# Line_detector_sensor.net
KiCad netlist of a schematic drawn in Altium Designer
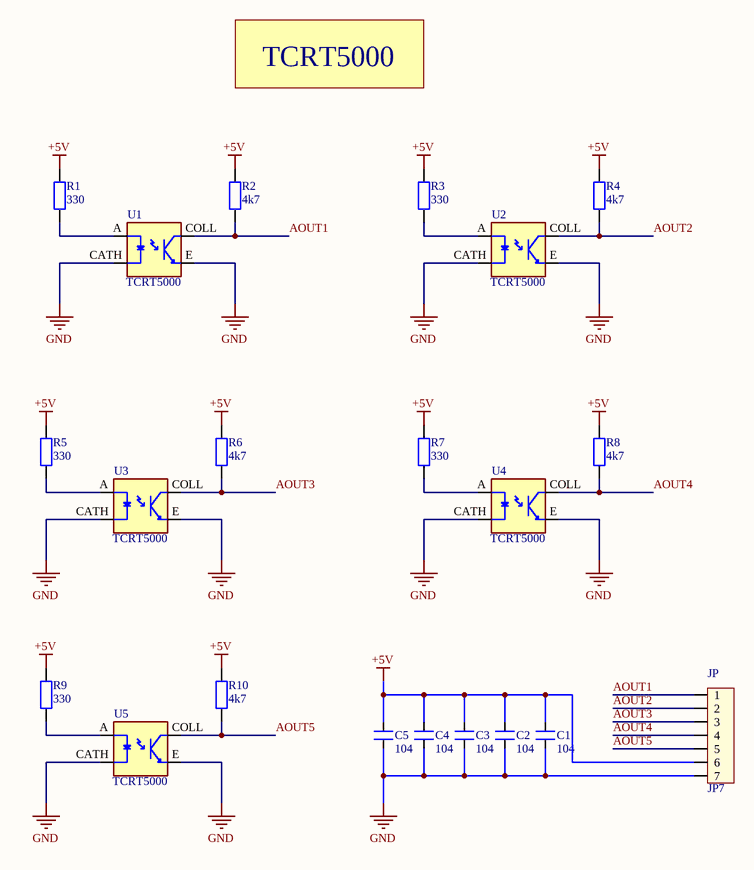
[diagram p0: Line_detector_sensor.SchDoc]

(export (version "E")
  (design (tool "Eeschema 10.0.6"))
  (components
    (comp (ref "C1")
      (value "104")
      (footprint "CN2")
      (description "Cap np 104 => 105pF")
      (libsource (lib "syhaunguyen") (part "CN2"))
    )
    (comp (ref "C2")
      (value "104")
      (footprint "CN2")
      (description "Cap np 104 => 105pF")
      (libsource (lib "syhaunguyen") (part "CN2"))
    )
    (comp (ref "C3")
      (value "104")
      (footprint "CN2")
      (description "Cap np 104 => 105pF")
      (libsource (lib "syhaunguyen") (part "CN2"))
    )
    (comp (ref "C4")
      (value "104")
      (footprint "CN2")
      (description "Cap np 104 => 105pF")
      (libsource (lib "syhaunguyen") (part "CN2"))
    )
    (comp (ref "C5")
      (value "104")
      (footprint "CN2")
      (description "Cap np 104 => 105pF")
      (libsource (lib "syhaunguyen") (part "CN2"))
    )
    (comp (ref "JP")
      (value "JP7")
      (footprint "CON7")
      (description "Connector 7")
      (libsource (lib "syhaunguyen") (part "Con7"))
    )
    (comp (ref "R1")
      (value "330")
      (footprint "R1/4W")
      (description "Resistor 1/4W")
      (libsource (lib "syhaunguyen") (part "R1/4W"))
    )
    (comp (ref "R2")
      (value "4k7")
      (footprint "R1/4W")
      (description "Resistor 1/4W")
      (libsource (lib "syhaunguyen") (part "R1/4W"))
    )
    (comp (ref "R3")
      (value "330")
      (footprint "R1/4W")
      (description "Resistor 1/4W")
      (libsource (lib "syhaunguyen") (part "R1/4W"))
    )
    (comp (ref "R4")
      (value "4k7")
      (footprint "R1/4W")
      (description "Resistor 1/4W")
      (libsource (lib "syhaunguyen") (part "R1/4W"))
    )
    (comp (ref "R5")
      (value "330")
      (footprint "R1/4W")
      (description "Resistor 1/4W")
      (libsource (lib "syhaunguyen") (part "R1/4W"))
    )
    (comp (ref "R6")
      (value "4k7")
      (footprint "R1/4W")
      (description "Resistor 1/4W")
      (libsource (lib "syhaunguyen") (part "R1/4W"))
    )
    (comp (ref "R7")
      (value "330")
      (footprint "R1/4W")
      (description "Resistor 1/4W")
      (libsource (lib "syhaunguyen") (part "R1/4W"))
    )
    (comp (ref "R8")
      (value "4k7")
      (footprint "R1/4W")
      (description "Resistor 1/4W")
      (libsource (lib "syhaunguyen") (part "R1/4W"))
    )
    (comp (ref "R9")
      (value "330")
      (footprint "R1/4W")
      (description "Resistor 1/4W")
      (libsource (lib "syhaunguyen") (part "R1/4W"))
    )
    (comp (ref "R10")
      (value "4k7")
      (footprint "R1/4W")
      (description "Resistor 1/4W")
      (libsource (lib "syhaunguyen") (part "R1/4W"))
    )
    (comp (ref "U1")
      (value "TCRT5000")
      (footprint "OPTO_TCRT5000")
      (description "950 nm 60 mA Through Hole Reflective Optical Sensor with Transistor Output")
      (libsource (lib "TCRT5000") (part "TCRT5000"))
    )
    (comp (ref "U2")
      (value "TCRT5000")
      (footprint "OPTO_TCRT5000")
      (description "950 nm 60 mA Through Hole Reflective Optical Sensor with Transistor Output")
      (libsource (lib "TCRT5000") (part "TCRT5000"))
    )
    (comp (ref "U3")
      (value "TCRT5000")
      (footprint "OPTO_TCRT5000")
      (description "950 nm 60 mA Through Hole Reflective Optical Sensor with Transistor Output")
      (libsource (lib "TCRT5000") (part "TCRT5000"))
    )
    (comp (ref "U4")
      (value "TCRT5000")
      (footprint "OPTO_TCRT5000")
      (description "950 nm 60 mA Through Hole Reflective Optical Sensor with Transistor Output")
      (libsource (lib "TCRT5000") (part "TCRT5000"))
    )
    (comp (ref "U5")
      (value "TCRT5000")
      (footprint "OPTO_TCRT5000")
      (description "950 nm 60 mA Through Hole Reflective Optical Sensor with Transistor Output")
      (libsource (lib "TCRT5000") (part "TCRT5000"))
    )
  )
  (nets
    (net (code "1") (name "+5V") (class "Default")
      (node (ref "C1") (pin "2") (pinfunction "2_2") (pintype "passive"))
      (node (ref "C2") (pin "2") (pinfunction "2_2") (pintype "passive"))
      (node (ref "C3") (pin "2") (pinfunction "2_2") (pintype "passive"))
      (node (ref "C4") (pin "2") (pinfunction "2_2") (pintype "passive"))
      (node (ref "C5") (pin "2") (pinfunction "2_2") (pintype "passive"))
      (node (ref "JP") (pin "6") (pinfunction "6_6") (pintype "passive"))
      (node (ref "R1") (pin "2") (pinfunction "2_2") (pintype "passive"))
      (node (ref "R10") (pin "2") (pinfunction "2_2") (pintype "passive"))
      (node (ref "R2") (pin "2") (pinfunction "2_2") (pintype "passive"))
      (node (ref "R3") (pin "2") (pinfunction "2_2") (pintype "passive"))
      (node (ref "R4") (pin "2") (pinfunction "2_2") (pintype "passive"))
      (node (ref "R5") (pin "2") (pinfunction "2_2") (pintype "passive"))
      (node (ref "R6") (pin "2") (pinfunction "2_2") (pintype "passive"))
      (node (ref "R7") (pin "2") (pinfunction "2_2") (pintype "passive"))
      (node (ref "R8") (pin "2") (pinfunction "2_2") (pintype "passive"))
      (node (ref "R9") (pin "2") (pinfunction "2_2") (pintype "passive"))
    )
    (net (code "2") (name "/AOUT1") (class "Default")
      (node (ref "JP") (pin "1") (pinfunction "1_1") (pintype "passive"))
      (node (ref "R2") (pin "1") (pinfunction "1_1") (pintype "passive"))
      (node (ref "U1") (pin "COLL") (pinfunction "COLL_COLL") (pintype "passive"))
    )
    (net (code "3") (name "/AOUT2") (class "Default")
      (node (ref "JP") (pin "2") (pinfunction "2_2") (pintype "passive"))
      (node (ref "R4") (pin "1") (pinfunction "1_1") (pintype "passive"))
      (node (ref "U2") (pin "COLL") (pinfunction "COLL_COLL") (pintype "passive"))
    )
    (net (code "4") (name "/AOUT3") (class "Default")
      (node (ref "JP") (pin "3") (pinfunction "3_3") (pintype "passive"))
      (node (ref "R6") (pin "1") (pinfunction "1_1") (pintype "passive"))
      (node (ref "U3") (pin "COLL") (pinfunction "COLL_COLL") (pintype "passive"))
    )
    (net (code "5") (name "/AOUT4") (class "Default")
      (node (ref "JP") (pin "4") (pinfunction "4_4") (pintype "passive"))
      (node (ref "R8") (pin "1") (pinfunction "1_1") (pintype "passive"))
      (node (ref "U4") (pin "COLL") (pinfunction "COLL_COLL") (pintype "passive"))
    )
    (net (code "6") (name "/AOUT5") (class "Default")
      (node (ref "JP") (pin "5") (pinfunction "5_5") (pintype "passive"))
      (node (ref "R10") (pin "1") (pinfunction "1_1") (pintype "passive"))
      (node (ref "U5") (pin "COLL") (pinfunction "COLL_COLL") (pintype "passive"))
    )
    (net (code "7") (name "GND") (class "Default")
      (node (ref "C1") (pin "1") (pinfunction "1_1") (pintype "passive"))
      (node (ref "C2") (pin "1") (pinfunction "1_1") (pintype "passive"))
      (node (ref "C3") (pin "1") (pinfunction "1_1") (pintype "passive"))
      (node (ref "C4") (pin "1") (pinfunction "1_1") (pintype "passive"))
      (node (ref "C5") (pin "1") (pinfunction "1_1") (pintype "passive"))
      (node (ref "JP") (pin "7") (pinfunction "7_7") (pintype "passive"))
      (node (ref "U1") (pin "CATH") (pinfunction "CATH_CATH") (pintype "passive"))
      (node (ref "U1") (pin "E") (pinfunction "E_E") (pintype "passive"))
      (node (ref "U2") (pin "CATH") (pinfunction "CATH_CATH") (pintype "passive"))
      (node (ref "U2") (pin "E") (pinfunction "E_E") (pintype "passive"))
      (node (ref "U3") (pin "CATH") (pinfunction "CATH_CATH") (pintype "passive"))
      (node (ref "U3") (pin "E") (pinfunction "E_E") (pintype "passive"))
      (node (ref "U4") (pin "CATH") (pinfunction "CATH_CATH") (pintype "passive"))
      (node (ref "U4") (pin "E") (pinfunction "E_E") (pintype "passive"))
      (node (ref "U5") (pin "CATH") (pinfunction "CATH_CATH") (pintype "passive"))
      (node (ref "U5") (pin "E") (pinfunction "E_E") (pintype "passive"))
    )
    (net (code "8") (name "Net-(R1-Pad1)") (class "Default")
      (node (ref "R1") (pin "1") (pinfunction "1_1") (pintype "passive"))
      (node (ref "U1") (pin "A") (pinfunction "A_A") (pintype "passive"))
    )
    (net (code "9") (name "Net-(R3-Pad1)") (class "Default")
      (node (ref "R3") (pin "1") (pinfunction "1_1") (pintype "passive"))
      (node (ref "U2") (pin "A") (pinfunction "A_A") (pintype "passive"))
    )
    (net (code "10") (name "Net-(R5-Pad1)") (class "Default")
      (node (ref "R5") (pin "1") (pinfunction "1_1") (pintype "passive"))
      (node (ref "U3") (pin "A") (pinfunction "A_A") (pintype "passive"))
    )
    (net (code "11") (name "Net-(R7-Pad1)") (class "Default")
      (node (ref "R7") (pin "1") (pinfunction "1_1") (pintype "passive"))
      (node (ref "U4") (pin "A") (pinfunction "A_A") (pintype "passive"))
    )
    (net (code "12") (name "Net-(R9-Pad1)") (class "Default")
      (node (ref "R9") (pin "1") (pinfunction "1_1") (pintype "passive"))
      (node (ref "U5") (pin "A") (pinfunction "A_A") (pintype "passive"))
    )
  )
)
